# 4_-_Ethernet_PHY.net
KiCad netlist of a schematic drawn in Altium Designer
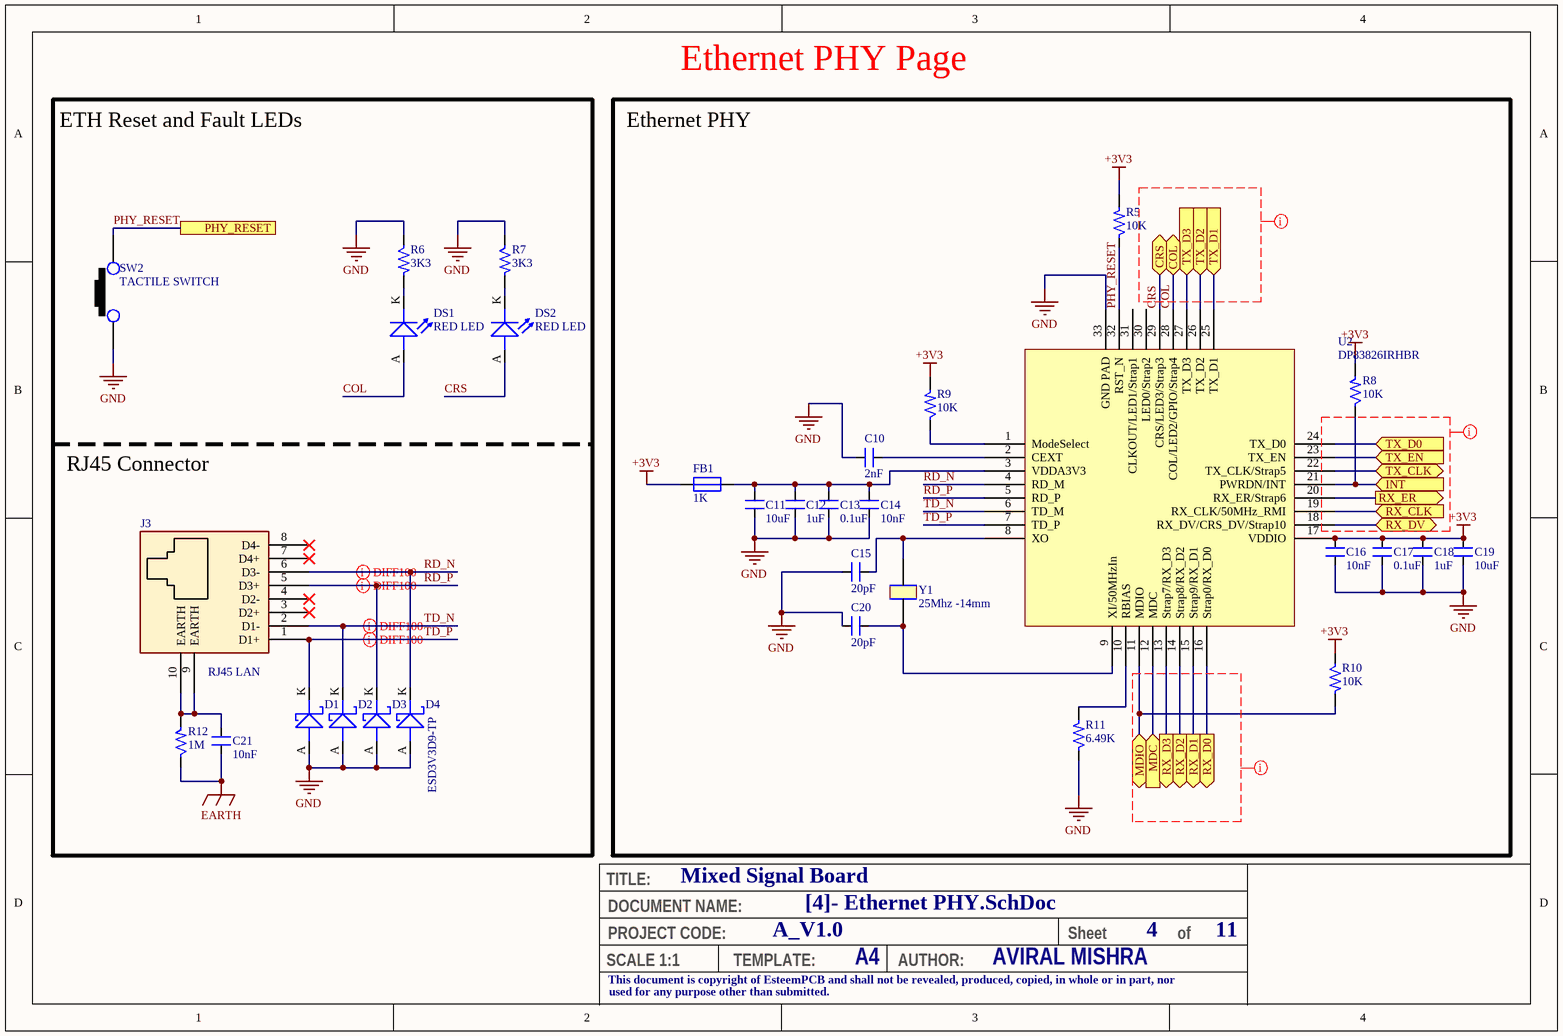
[diagram p0: [4]- Ethernet PHY.SchDoc]

(export (version "E")
  (design (tool "Eeschema 10.0.6"))
  (components
    (comp (ref "C10")
      (value "2nF")
      (footprint "CAP_0805")
      (description "2000pF ±10% 50V Ceramic Capacitor X7R 0805 (2012 Metric)")
      (fields
        (field (name "MANUFACTURER") "Samsung Electro-Mechanics")
        (field (name "MANUFACTURER PART NUMBER") "CL21B202KBANNNC")
      )
      (libsource (lib "ESTEEMPCBLIB") (part "CAP_2nF-50V-10%-0805"))
    )
    (comp (ref "C11")
      (value "10uF")
      (footprint "CAP_1206")
      (description "10µF ±10% 50V Ceramic Capacitor X7R 1206 (3216 Metric)")
      (fields
        (field (name "MANUFACTURER") "KEMET")
        (field (name "MANUFACTURER PART NUMBER") "CL31B106KBHNNNE")
      )
      (libsource (lib "ESTEEMPCBLIB") (part "CAP_10uF-50V-10%-1206"))
    )
    (comp (ref "C12")
      (value "1uF")
      (footprint "CAP_0805")
      (description "1µF ±5% 50V Ceramic Capacitor X7R 0805 (2012 Metric)")
      (fields
        (field (name "MANUFACTURER") "Samsung")
        (field (name "MANUFACTURER PART NUMBER") "CC0805JKX7R9BB105")
      )
      (libsource (lib "ESTEEMPCBLIB") (part "CAP_1uF-50V-5%-0805"))
    )
    (comp (ref "C13")
      (value "0.1uF")
      (footprint "CAP_0805")
      (description "0.1µF ±10% 50V Ceramic Capacitor X7R 0805 (2012 Metric)")
      (fields
        (field (name "MANUFACTURER") "Samsung")
        (field (name "MANUFACTURER PART NUMBER") "CL21B104KBCNNNC")
      )
      (libsource (lib "ESTEEMPCBLIB") (part "CAP_0.1uF-50V-10%-0805"))
    )
    (comp (ref "C14")
      (value "10nF")
      (footprint "CAP_0805")
      (description "10000pF ±10% 50V Ceramic Capacitor X7R 0805 (2012 Metric)")
      (fields
        (field (name "MANUFACTURER") "Samsung")
        (field (name "MANUFACTURER PART NUMBER") "C0805C103K5RECAUTO")
      )
      (libsource (lib "ESTEEMPCBLIB") (part "CAP_10nF-50V-10%-0805"))
    )
    (comp (ref "C15")
      (value "20pF")
      (footprint "CAP_0805")
      (description "±10% 50V Ceramic Capacitor C0G, NP0 0805 (2012 Metric)")
      (fields
        (field (name "MANUFACTURER") "AVX Corporation")
        (field (name "MANUFACTURER PART NUMBER") "08055A200KAT2A")
      )
      (libsource (lib "ESTEEMPCBLIB") (part "CAP_20pF-50V-10%-0805"))
    )
    (comp (ref "C16")
      (value "10nF")
      (footprint "CAP_0805")
      (description "10000pF ±10% 50V Ceramic Capacitor X7R 0805 (2012 Metric)")
      (fields
        (field (name "MANUFACTURER") "Samsung")
        (field (name "MANUFACTURER PART NUMBER") "C0805C103K5RECAUTO")
      )
      (libsource (lib "ESTEEMPCBLIB") (part "CAP_10nF-50V-10%-0805"))
    )
    (comp (ref "C17")
      (value "0.1uF")
      (footprint "CAP_0805")
      (description "0.1µF ±10% 50V Ceramic Capacitor X7R 0805 (2012 Metric)")
      (fields
        (field (name "MANUFACTURER") "Samsung")
        (field (name "MANUFACTURER PART NUMBER") "CL21B104KBCNNNC")
      )
      (libsource (lib "ESTEEMPCBLIB") (part "CAP_0.1uF-50V-10%-0805"))
    )
    (comp (ref "C18")
      (value "1uF")
      (footprint "CAP_0805")
      (description "1µF ±5% 50V Ceramic Capacitor X7R 0805 (2012 Metric)")
      (fields
        (field (name "MANUFACTURER") "Samsung")
        (field (name "MANUFACTURER PART NUMBER") "CC0805JKX7R9BB105")
      )
      (libsource (lib "ESTEEMPCBLIB") (part "CAP_1uF-50V-5%-0805"))
    )
    (comp (ref "C19")
      (value "10uF")
      (footprint "CAP_1206")
      (description "10µF ±10% 50V Ceramic Capacitor X7R 1206 (3216 Metric)")
      (fields
        (field (name "MANUFACTURER") "KEMET")
        (field (name "MANUFACTURER PART NUMBER") "CL31B106KBHNNNE")
      )
      (libsource (lib "ESTEEMPCBLIB") (part "CAP_10uF-50V-10%-1206"))
    )
    (comp (ref "C20")
      (value "20pF")
      (footprint "CAP_0805")
      (description "±10% 50V Ceramic Capacitor C0G, NP0 0805 (2012 Metric)")
      (fields
        (field (name "MANUFACTURER") "AVX Corporation")
        (field (name "MANUFACTURER PART NUMBER") "08055A200KAT2A")
      )
      (libsource (lib "ESTEEMPCBLIB") (part "CAP_20pF-50V-10%-0805"))
    )
    (comp (ref "C21")
      (value "10nF")
      (footprint "CAP_P196_102X287_H332_RAD_TH")
      (description "10000pF ±10% 1000V (1kV) Ceramic Capacitor X7R Radial")
      (fields
        (field (name "MANUFACTURER") "Yageo")
        (field (name "MANUFACTURER PART NUMBER") "RDER73A103K2K1H03B")
      )
      (libsource (lib "ESTEEMPCBLIB") (part "CAP_10nF-1KV-10%-RAD-TH"))
    )
    (comp (ref "D1")
      (value "ESD3V3D9-TP")
      (footprint "DIO_SOD-923")
      (description "8.8V Clamp 5A (8/20µs) Ipp Tvs Diode Surface Mount SOD-923")
      (fields (field (name "MANUFACTURER") "Micro Commercial Co"))
      (libsource (lib "ESTEEMPCBLIB") (part "DIO-T_3.3V-8.8V-SOD923"))
    )
    (comp (ref "D2")
      (value "ESD3V3D9-TP")
      (footprint "DIO_SOD-923")
      (description "8.8V Clamp 5A (8/20µs) Ipp Tvs Diode Surface Mount SOD-923")
      (fields (field (name "MANUFACTURER") "Micro Commercial Co"))
      (libsource (lib "ESTEEMPCBLIB") (part "DIO-T_3.3V-8.8V-SOD923"))
    )
    (comp (ref "D3")
      (value "ESD3V3D9-TP")
      (footprint "DIO_SOD-923")
      (description "8.8V Clamp 5A (8/20µs) Ipp Tvs Diode Surface Mount SOD-923")
      (fields (field (name "MANUFACTURER") "Micro Commercial Co"))
      (libsource (lib "ESTEEMPCBLIB") (part "DIO-T_3.3V-8.8V-SOD923"))
    )
    (comp (ref "D4")
      (value "ESD3V3D9-TP")
      (footprint "DIO_SOD-923")
      (description "8.8V Clamp 5A (8/20µs) Ipp Tvs Diode Surface Mount SOD-923")
      (fields (field (name "MANUFACTURER") "Micro Commercial Co"))
      (libsource (lib "ESTEEMPCBLIB") (part "DIO-T_3.3V-8.8V-SOD923"))
    )
    (comp (ref "DS1")
      (value "RED LED")
      (footprint "LED_0805")
      (description "Red 631nm LED Indication - Discrete 2V 0805 (2012 Metric)")
      (fields
        (field (name "MANUFACTURER") "Vishay Lite-On")
        (field (name "MANUFACTURER PART NUMBER") "LTST-C171KRKT")
      )
      (libsource (lib "ESTEEMPCBLIB") (part "LED_RED-2V-20mA-0805"))
    )
    (comp (ref "DS2")
      (value "RED LED")
      (footprint "LED_0805")
      (description "Red 631nm LED Indication - Discrete 2V 0805 (2012 Metric)")
      (fields
        (field (name "MANUFACTURER") "Vishay Lite-On")
        (field (name "MANUFACTURER PART NUMBER") "LTST-C171KRKT")
      )
      (libsource (lib "ESTEEMPCBLIB") (part "LED_RED-2V-20mA-0805"))
    )
    (comp (ref "FB1")
      (value "1K")
      (footprint "IND_0805")
      (description "1 kOhms @ 100MHz 1 Power Line Ferrite Bead 0805 (2012 Metric) 1.6A")
      (fields
        (field (name "MANUFACTURER") "Laird")
        (field (name "MANUFACTURER PART NUMBER") "BLM21SP102SH1D")
      )
      (libsource (lib "ESTEEMPCBLIB") (part "FB_1K-100MHZ-1.6A-0805"))
    )
    (comp (ref "J3")
      (value "RJ45 LAN")
      (footprint "CON10_P106_RJ45_TH_ST")
      (description "8 Pins, 2 Row 2.54mm Pitch, right angle Connector, male")
      (fields
        (field (name "MANUFACTURER") "Assmann")
        (field (name "MANUFACTURER PART NUMBER") "A-2004-2-4-LPS-N-R")
      )
      (libsource (lib "ESTEEMPCBLIB") (part "CON-SKT-RJ_8C8P-RA-TH"))
    )
    (comp (ref "R5")
      (value "10K")
      (footprint "RES_0603")
      (description "10 kOhms ±1% 0.1W, 1/10W Chip Resistor 0603 (1608 Metric) Automotive AEC-Q200 Thick Film")
      (fields (field (name "MANUFACTURER") "Walsin") (field (name "MANUFACTURER PART NUMBER") "WR06X1002FTL"))
      (libsource (lib "ESTEEMPCBLIB") (part "RES_10K-0.1W-1%-0603"))
    )
    (comp (ref "R6")
      (value "3K3")
      (footprint "RES_0603")
      (description "3.3 kOhms ±1% 0.1W, 1/10W Chip Resistor 0603 (1608 Metric) Automotive AEC-Q200 Thick Film")
      (fields (field (name "MANUFACTURER") "Wilson") (field (name "MANUFACTURER PART NUMBER") "WR06X3301FTL"))
      (libsource (lib "ESTEEMPCBLIB") (part "RES_3.3K-0.1W-1%-0603"))
    )
    (comp (ref "R7")
      (value "3K3")
      (footprint "RES_0603")
      (description "3.3 kOhms ±1% 0.1W, 1/10W Chip Resistor 0603 (1608 Metric) Automotive AEC-Q200 Thick Film")
      (fields (field (name "MANUFACTURER") "Wilson") (field (name "MANUFACTURER PART NUMBER") "WR06X3301FTL"))
      (libsource (lib "ESTEEMPCBLIB") (part "RES_3.3K-0.1W-1%-0603"))
    )
    (comp (ref "R8")
      (value "10K")
      (footprint "RES_0603")
      (description "10 kOhms ±1% 0.1W, 1/10W Chip Resistor 0603 (1608 Metric) Automotive AEC-Q200 Thick Film")
      (fields (field (name "MANUFACTURER") "Walsin") (field (name "MANUFACTURER PART NUMBER") "WR06X1002FTL"))
      (libsource (lib "ESTEEMPCBLIB") (part "RES_10K-0.1W-1%-0603"))
    )
    (comp (ref "R9")
      (value "10K")
      (footprint "RES_0603")
      (description "10 kOhms ±1% 0.1W, 1/10W Chip Resistor 0603 (1608 Metric) Automotive AEC-Q200 Thick Film")
      (fields (field (name "MANUFACTURER") "Walsin") (field (name "MANUFACTURER PART NUMBER") "WR06X1002FTL"))
      (libsource (lib "ESTEEMPCBLIB") (part "RES_10K-0.1W-1%-0603"))
    )
    (comp (ref "R10")
      (value "10K")
      (footprint "RES_0603")
      (description "10 kOhms ±1% 0.1W, 1/10W Chip Resistor 0603 (1608 Metric) Automotive AEC-Q200 Thick Film")
      (fields (field (name "MANUFACTURER") "Walsin") (field (name "MANUFACTURER PART NUMBER") "WR06X1002FTL"))
      (libsource (lib "ESTEEMPCBLIB") (part "RES_10K-0.1W-1%-0603"))
    )
    (comp (ref "R11")
      (value "6.49K")
      (footprint "RES_0805")
      (description "6.49 kOhms ±1% 0.125W, 1/8W Chip Resistor 0805 (2012 Metric) Moisture Resistant Thick Film")
      (fields
        (field (name "MANUFACTURER") "Stackpole Electronics")
        (field (name "MANUFACTURER PART NUMBER") "RC0805FR-076K49L")
      )
      (libsource (lib "ESTEEMPCBLIB") (part "RES_6.49K-0.125W-1%-0805"))
    )
    (comp (ref "R12")
      (value "1M")
      (footprint "RES_1206")
      (fields (field (name "MANUFACTURER") "Walsin") (field (name "MANUFACTURER PART NUMBER") "WR12X1004FTL"))
      (libsource (lib "ESTEEMPCBLIB") (part "RES_1M-0.25W-1%-1206"))
    )
    (comp (ref "SW2")
      (value "TACTILE SWITCH")
      (footprint "SW_342_SMD")
      (description "Tactile Switch SPST-NO Top Actuated Surface Mount")
      (fields
        (field (name "MANUFACTURER") "ITT C&K")
        (field (name "MANUFACTURER PART NUMBER") "RS-282G05A3-SMRT")
      )
      (libsource (lib "ESTEEMPCBLIB") (part "SW1_RS-282G05A3-SMRT-SMD"))
    )
    (comp (ref "U2")
      (value "DP83826IRHBR")
      (footprint "VQFN32_19_218_23X9_SMD")
      (fields (field (name "MANUFACTURER") "Texas Instruments"))
      (libsource (lib "ESTEEMPCBLIB") (part "IC_DP83826IRHBR"))
    )
    (comp (ref "Y1")
      (value "25Mhz -14mm")
      (footprint "XTAL_314_240X47_SMD")
      (description "25MHz ±30ppm Crystal 20pF 30 Ohms HC-49/US")
      (fields
        (field (name "MANUFACTURER") "Abracon")
        (field (name "MANUFACTURER PART NUMBER") "FOXSDLF/250F-20")
      )
      (libsource (lib "ESTEEMPCBLIB") (part "XTAL_25Mhz-FOXSDLF/250F-20"))
    )
  )
  (nets
    (net (code "1") (name "+3V3") (class "Default")
      (node (ref "C16") (pin "2") (pinfunction "2_2") (pintype "passive"))
      (node (ref "C17") (pin "2") (pinfunction "2_2") (pintype "passive"))
      (node (ref "C18") (pin "2") (pinfunction "2_2") (pintype "passive"))
      (node (ref "C19") (pin "2") (pinfunction "2_2") (pintype "passive"))
      (node (ref "FB1") (pin "1") (pinfunction "1_1") (pintype "passive"))
      (node (ref "R10") (pin "1") (pinfunction "1_1") (pintype "passive"))
      (node (ref "R5") (pin "2") (pinfunction "2_2") (pintype "passive"))
      (node (ref "R8") (pin "2") (pinfunction "2_2") (pintype "passive"))
      (node (ref "R9") (pin "2") (pinfunction "2_2") (pintype "passive"))
      (node (ref "U2") (pin "17") (pinfunction "VDDIO_17") (pintype "passive"))
    )
    (net (code "2") (name "/COL") (class "Default")
      (node (ref "DS1") (pin "A") (pinfunction "ANODE_A") (pintype "passive"))
      (node (ref "U2") (pin "28") (pinfunction "COL/LED2/GPIO/Strap4_28") (pintype "passive"))
    )
    (net (code "3") (name "/CRS") (class "Default")
      (node (ref "DS2") (pin "A") (pinfunction "ANODE_A") (pintype "passive"))
      (node (ref "U2") (pin "29") (pinfunction "CRS/LED3/Strap3_29") (pintype "passive"))
    )
    (net (code "4") (name "/INT") (class "Default")
      (node (ref "R8") (pin "1") (pinfunction "1_1") (pintype "passive"))
      (node (ref "U2") (pin "21") (pinfunction "PWRDN/INT_21") (pintype "passive"))
    )
    (net (code "5") (name "/MDC") (class "Default")
      (node (ref "U2") (pin "12") (pinfunction "MDC_12") (pintype "passive"))
    )
    (net (code "6") (name "/MDIO") (class "Default")
      (node (ref "R10") (pin "2") (pinfunction "2_2") (pintype "passive"))
      (node (ref "U2") (pin "11") (pinfunction "MDIO_11") (pintype "passive"))
    )
    (net (code "7") (name "/PHY_RESET") (class "Default")
      (node (ref "R5") (pin "1") (pinfunction "1_1") (pintype "passive"))
      (node (ref "SW2") (pin "2") (pinfunction "2_2") (pintype "passive"))
      (node (ref "U2") (pin "32") (pinfunction "RST_N_32") (pintype "passive"))
    )
    (net (code "8") (name "/RD_N") (class "Default")
      (node (ref "D4") (pin "K") (pinfunction "K_K") (pintype "passive"))
      (node (ref "J3") (pin "6") (pinfunction "D3-_6") (pintype "passive"))
      (node (ref "U2") (pin "4") (pinfunction "RD_M_4") (pintype "passive"))
    )
    (net (code "9") (name "/RD_P") (class "Default")
      (node (ref "D3") (pin "K") (pinfunction "K_K") (pintype "passive"))
      (node (ref "J3") (pin "5") (pinfunction "D3+_5") (pintype "passive"))
      (node (ref "U2") (pin "5") (pinfunction "RD_P_5") (pintype "passive"))
    )
    (net (code "10") (name "/RX_CLK") (class "Default")
      (node (ref "U2") (pin "19") (pinfunction "RX_CLK/50MHz_RMI_19") (pintype "passive"))
    )
    (net (code "11") (name "/RX_D0") (class "Default")
      (node (ref "U2") (pin "16") (pinfunction "Strap0/RX_D0_16") (pintype "passive"))
    )
    (net (code "12") (name "/RX_D1") (class "Default")
      (node (ref "U2") (pin "15") (pinfunction "Strap9/RX_D1_15") (pintype "passive"))
    )
    (net (code "13") (name "/RX_D2") (class "Default")
      (node (ref "U2") (pin "14") (pinfunction "Strap8/RX_D2_14") (pintype "passive"))
    )
    (net (code "14") (name "/RX_D3") (class "Default")
      (node (ref "U2") (pin "13") (pinfunction "Strap7/RX_D3_13") (pintype "passive"))
    )
    (net (code "15") (name "/RX_DV") (class "Default")
      (node (ref "U2") (pin "18") (pinfunction "RX_DV/CRS_DV/Strap10_18") (pintype "passive"))
    )
    (net (code "16") (name "/RX_ER") (class "Default")
      (node (ref "U2") (pin "20") (pinfunction "RX_ER/Strap6_20") (pintype "passive"))
    )
    (net (code "17") (name "/TD_N") (class "Default")
      (node (ref "D2") (pin "K") (pinfunction "K_K") (pintype "passive"))
      (node (ref "J3") (pin "2") (pinfunction "D1-_2") (pintype "passive"))
      (node (ref "U2") (pin "6") (pinfunction "TD_M_6") (pintype "passive"))
    )
    (net (code "18") (name "/TD_P") (class "Default")
      (node (ref "D1") (pin "K") (pinfunction "K_K") (pintype "passive"))
      (node (ref "J3") (pin "1") (pinfunction "D1+_1") (pintype "passive"))
      (node (ref "U2") (pin "7") (pinfunction "TD_P_7") (pintype "passive"))
    )
    (net (code "19") (name "/TX_CLK") (class "Default")
      (node (ref "U2") (pin "22") (pinfunction "TX_CLK/Strap5_22") (pintype "passive"))
    )
    (net (code "20") (name "/TX_D0") (class "Default")
      (node (ref "U2") (pin "24") (pinfunction "TX_D0_24") (pintype "passive"))
    )
    (net (code "21") (name "/TX_D1") (class "Default")
      (node (ref "U2") (pin "25") (pinfunction "TX_D1_25") (pintype "passive"))
    )
    (net (code "22") (name "/TX_D2") (class "Default")
      (node (ref "U2") (pin "26") (pinfunction "TX_D2_26") (pintype "passive"))
    )
    (net (code "23") (name "/TX_D3") (class "Default")
      (node (ref "U2") (pin "27") (pinfunction "TX_D3_27") (pintype "passive"))
    )
    (net (code "24") (name "/TX_EN") (class "Default")
      (node (ref "U2") (pin "23") (pinfunction "TX_EN_23") (pintype "passive"))
    )
    (net (code "25") (name "EARTH") (class "Default")
      (node (ref "C21") (pin "1") (pinfunction "1_1") (pintype "passive"))
      (node (ref "R12") (pin "1") (pinfunction "1_1") (pintype "passive"))
    )
    (net (code "26") (name "GND") (class "Default")
      (node (ref "C10") (pin "1") (pinfunction "1_1") (pintype "passive"))
      (node (ref "C11") (pin "1") (pinfunction "1_1") (pintype "passive"))
      (node (ref "C12") (pin "1") (pinfunction "1_1") (pintype "passive"))
      (node (ref "C13") (pin "1") (pinfunction "1_1") (pintype "passive"))
      (node (ref "C14") (pin "1") (pinfunction "1_1") (pintype "passive"))
      (node (ref "C15") (pin "1") (pinfunction "1_1") (pintype "passive"))
      (node (ref "C16") (pin "1") (pinfunction "1_1") (pintype "passive"))
      (node (ref "C17") (pin "1") (pinfunction "1_1") (pintype "passive"))
      (node (ref "C18") (pin "1") (pinfunction "1_1") (pintype "passive"))
      (node (ref "C19") (pin "1") (pinfunction "1_1") (pintype "passive"))
      (node (ref "C20") (pin "1") (pinfunction "1_1") (pintype "passive"))
      (node (ref "D1") (pin "A") (pinfunction "A_A") (pintype "passive"))
      (node (ref "D2") (pin "A") (pinfunction "A_A") (pintype "passive"))
      (node (ref "D3") (pin "A") (pinfunction "A_A") (pintype "passive"))
      (node (ref "D4") (pin "A") (pinfunction "A_A") (pintype "passive"))
      (node (ref "R11") (pin "1") (pinfunction "1_1") (pintype "passive"))
      (node (ref "R6") (pin "1") (pinfunction "1_1") (pintype "passive"))
      (node (ref "R7") (pin "1") (pinfunction "1_1") (pintype "passive"))
      (node (ref "SW2") (pin "1") (pinfunction "1_1") (pintype "passive"))
      (node (ref "U2") (pin "33") (pinfunction "GND_PAD_33") (pintype "passive"))
    )
    (net (code "27") (name "Net-(C21-Pad2)") (class "Default")
      (node (ref "C21") (pin "2") (pinfunction "2_2") (pintype "passive"))
      (node (ref "J3") (pin "10") (pinfunction "EARTH_10") (pintype "passive"))
      (node (ref "J3") (pin "9") (pinfunction "EARTH_9") (pintype "passive"))
      (node (ref "R12") (pin "2") (pinfunction "2_2") (pintype "passive"))
    )
    (net (code "28") (name "Net-(DS1-CATHODE)") (class "Default")
      (node (ref "DS1") (pin "K") (pinfunction "CATHODE_K") (pintype "passive"))
      (node (ref "R6") (pin "2") (pinfunction "2_2") (pintype "passive"))
    )
    (net (code "29") (name "Net-(DS2-CATHODE)") (class "Default")
      (node (ref "DS2") (pin "K") (pinfunction "CATHODE_K") (pintype "passive"))
      (node (ref "R7") (pin "2") (pinfunction "2_2") (pintype "passive"))
    )
    (net (code "30") (name "Net-(U2-CEXT)") (class "Default")
      (node (ref "C10") (pin "2") (pinfunction "2_2") (pintype "passive"))
      (node (ref "U2") (pin "2") (pinfunction "CEXT_2") (pintype "passive"))
    )
    (net (code "31") (name "Net-(U2-ModeSelect)") (class "Default")
      (node (ref "R9") (pin "1") (pinfunction "1_1") (pintype "passive"))
      (node (ref "U2") (pin "1") (pinfunction "ModeSelect_1") (pintype "passive"))
    )
    (net (code "32") (name "Net-(U2-RBIAS)") (class "Default")
      (node (ref "R11") (pin "2") (pinfunction "2_2") (pintype "passive"))
      (node (ref "U2") (pin "10") (pinfunction "RBIAS_10") (pintype "passive"))
    )
    (net (code "33") (name "Net-(U2-VDDA3V3)") (class "Default")
      (node (ref "C11") (pin "2") (pinfunction "2_2") (pintype "passive"))
      (node (ref "C12") (pin "2") (pinfunction "2_2") (pintype "passive"))
      (node (ref "C13") (pin "2") (pinfunction "2_2") (pintype "passive"))
      (node (ref "C14") (pin "2") (pinfunction "2_2") (pintype "passive"))
      (node (ref "FB1") (pin "2") (pinfunction "2_2") (pintype "passive"))
      (node (ref "U2") (pin "3") (pinfunction "VDDA3V3_3") (pintype "passive"))
    )
    (net (code "34") (name "Net-(U2-XI{slash}50MHzIn)") (class "Default")
      (node (ref "C20") (pin "2") (pinfunction "2_2") (pintype "passive"))
      (node (ref "U2") (pin "9") (pinfunction "XI/50MHzIn_9") (pintype "passive"))
      (node (ref "Y1") (pin "1") (pinfunction "1_1") (pintype "passive"))
    )
    (net (code "35") (name "Net-(U2-XO)") (class "Default")
      (node (ref "C15") (pin "2") (pinfunction "2_2") (pintype "passive"))
      (node (ref "U2") (pin "8") (pinfunction "XO_8") (pintype "passive"))
      (node (ref "Y1") (pin "2") (pinfunction "2_2") (pintype "passive"))
    )
    (net (code "36") (name "unconnected-(J3-D2+-Pad3)") (class "Default")
      (node (ref "J3") (pin "3") (pinfunction "D2+_3") (pintype "passive+no_connect"))
    )
    (net (code "37") (name "unconnected-(J3-D2--Pad4)") (class "Default")
      (node (ref "J3") (pin "4") (pinfunction "D2-_4") (pintype "passive+no_connect"))
    )
    (net (code "38") (name "unconnected-(J3-D4+-Pad7)") (class "Default")
      (node (ref "J3") (pin "7") (pinfunction "D4+_7") (pintype "passive+no_connect"))
    )
    (net (code "39") (name "unconnected-(J3-D4--Pad8)") (class "Default")
      (node (ref "J3") (pin "8") (pinfunction "D4-_8") (pintype "passive+no_connect"))
    )
    (net (code "40") (name "unconnected-(U2-CLKOUT{slash}LED1{slash}Strap1-Pad31)") (class "Default")
      (node (ref "U2") (pin "31") (pinfunction "CLKOUT/LED1/Strap1_31") (pintype "passive"))
    )
    (net (code "41") (name "unconnected-(U2-LED0{slash}Strap2-Pad30)") (class "Default")
      (node (ref "U2") (pin "30") (pinfunction "LED0/Strap2_30") (pintype "passive"))
    )
  )
)
